# ECG_Patch.net
KiCad netlist of a schematic drawn in EAGLE
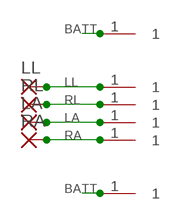
[diagram p0: schematic, sheet 1]

(export (version "E")
  (design (tool "Eeschema 10.0.6"))
  (components
    (comp (ref "LA")
      (value "1,6/0,8")
      (footprint "eagle-import:1,6_0,8")
      (libsource (lib "eagle-import") (part "1,6/0,8"))
    )
    (comp (ref "LL")
      (value "1,6/0,8")
      (footprint "eagle-import:1,6_0,8")
      (libsource (lib "eagle-import") (part "1,6/0,8"))
    )
    (comp (ref "P1")
      (value "PISTON_RA_TH")
      (footprint "eagle-import:PISTON_RA_TH")
      (libsource (lib "eagle-import") (part "PISTON_RA_TH"))
    )
    (comp (ref "P2")
      (value "PISTON_RA_TH")
      (footprint "eagle-import:PISTON_RA_TH")
      (libsource (lib "eagle-import") (part "PISTON_RA_TH"))
    )
    (comp (ref "P3")
      (value "PISTON_RA_TH")
      (footprint "eagle-import:PISTON_RA_TH")
      (libsource (lib "eagle-import") (part "PISTON_RA_TH"))
    )
    (comp (ref "P4")
      (value "PISTON_RA_TH")
      (footprint "eagle-import:PISTON_RA_TH")
      (libsource (lib "eagle-import") (part "PISTON_RA_TH"))
    )
    (comp (ref "P5")
      (value "PISTON_RA_TH")
      (footprint "eagle-import:PISTON_RA_TH")
      (libsource (lib "eagle-import") (part "PISTON_RA_TH"))
    )
    (comp (ref "P6")
      (value "PISTON_RA_TH")
      (footprint "eagle-import:PISTON_RA_TH")
      (libsource (lib "eagle-import") (part "PISTON_RA_TH"))
    )
    (comp (ref "RA")
      (value "1,6/0,8")
      (footprint "eagle-import:1,6_0,8")
      (libsource (lib "eagle-import") (part "1,6/0,8"))
    )
    (comp (ref "RL")
      (value "1,6/0,8")
      (footprint "eagle-import:1,6_0,8")
      (libsource (lib "eagle-import") (part "1,6/0,8"))
    )
  )
  (nets
    (net (code "1") (name "/BATT") (class "Default")
      (node (ref "P1") (pin "1") (pinfunction "1_1") (pintype "bidirectional"))
      (node (ref "P6") (pin "1") (pinfunction "1_1") (pintype "bidirectional"))
    )
    (net (code "2") (name "/LA") (class "Default")
      (node (ref "LA") (pin "1") (pinfunction "P_1") (pintype "passive"))
      (node (ref "P4") (pin "1") (pinfunction "1_1") (pintype "bidirectional"))
    )
    (net (code "3") (name "/LL") (class "Default")
      (node (ref "LL") (pin "1") (pinfunction "P_1") (pintype "passive"))
      (node (ref "P3") (pin "1") (pinfunction "1_1") (pintype "bidirectional"))
    )
    (net (code "4") (name "/RA") (class "Default")
      (node (ref "P5") (pin "1") (pinfunction "1_1") (pintype "bidirectional"))
      (node (ref "RA") (pin "1") (pinfunction "P_1") (pintype "passive"))
    )
    (net (code "5") (name "/RL") (class "Default")
      (node (ref "P2") (pin "1") (pinfunction "1_1") (pintype "bidirectional"))
      (node (ref "RL") (pin "1") (pinfunction "P_1") (pintype "passive"))
    )
  )
)
